# okenkovy_diskriminator.net
KiCad netlist of a schematic drawn in EAGLE
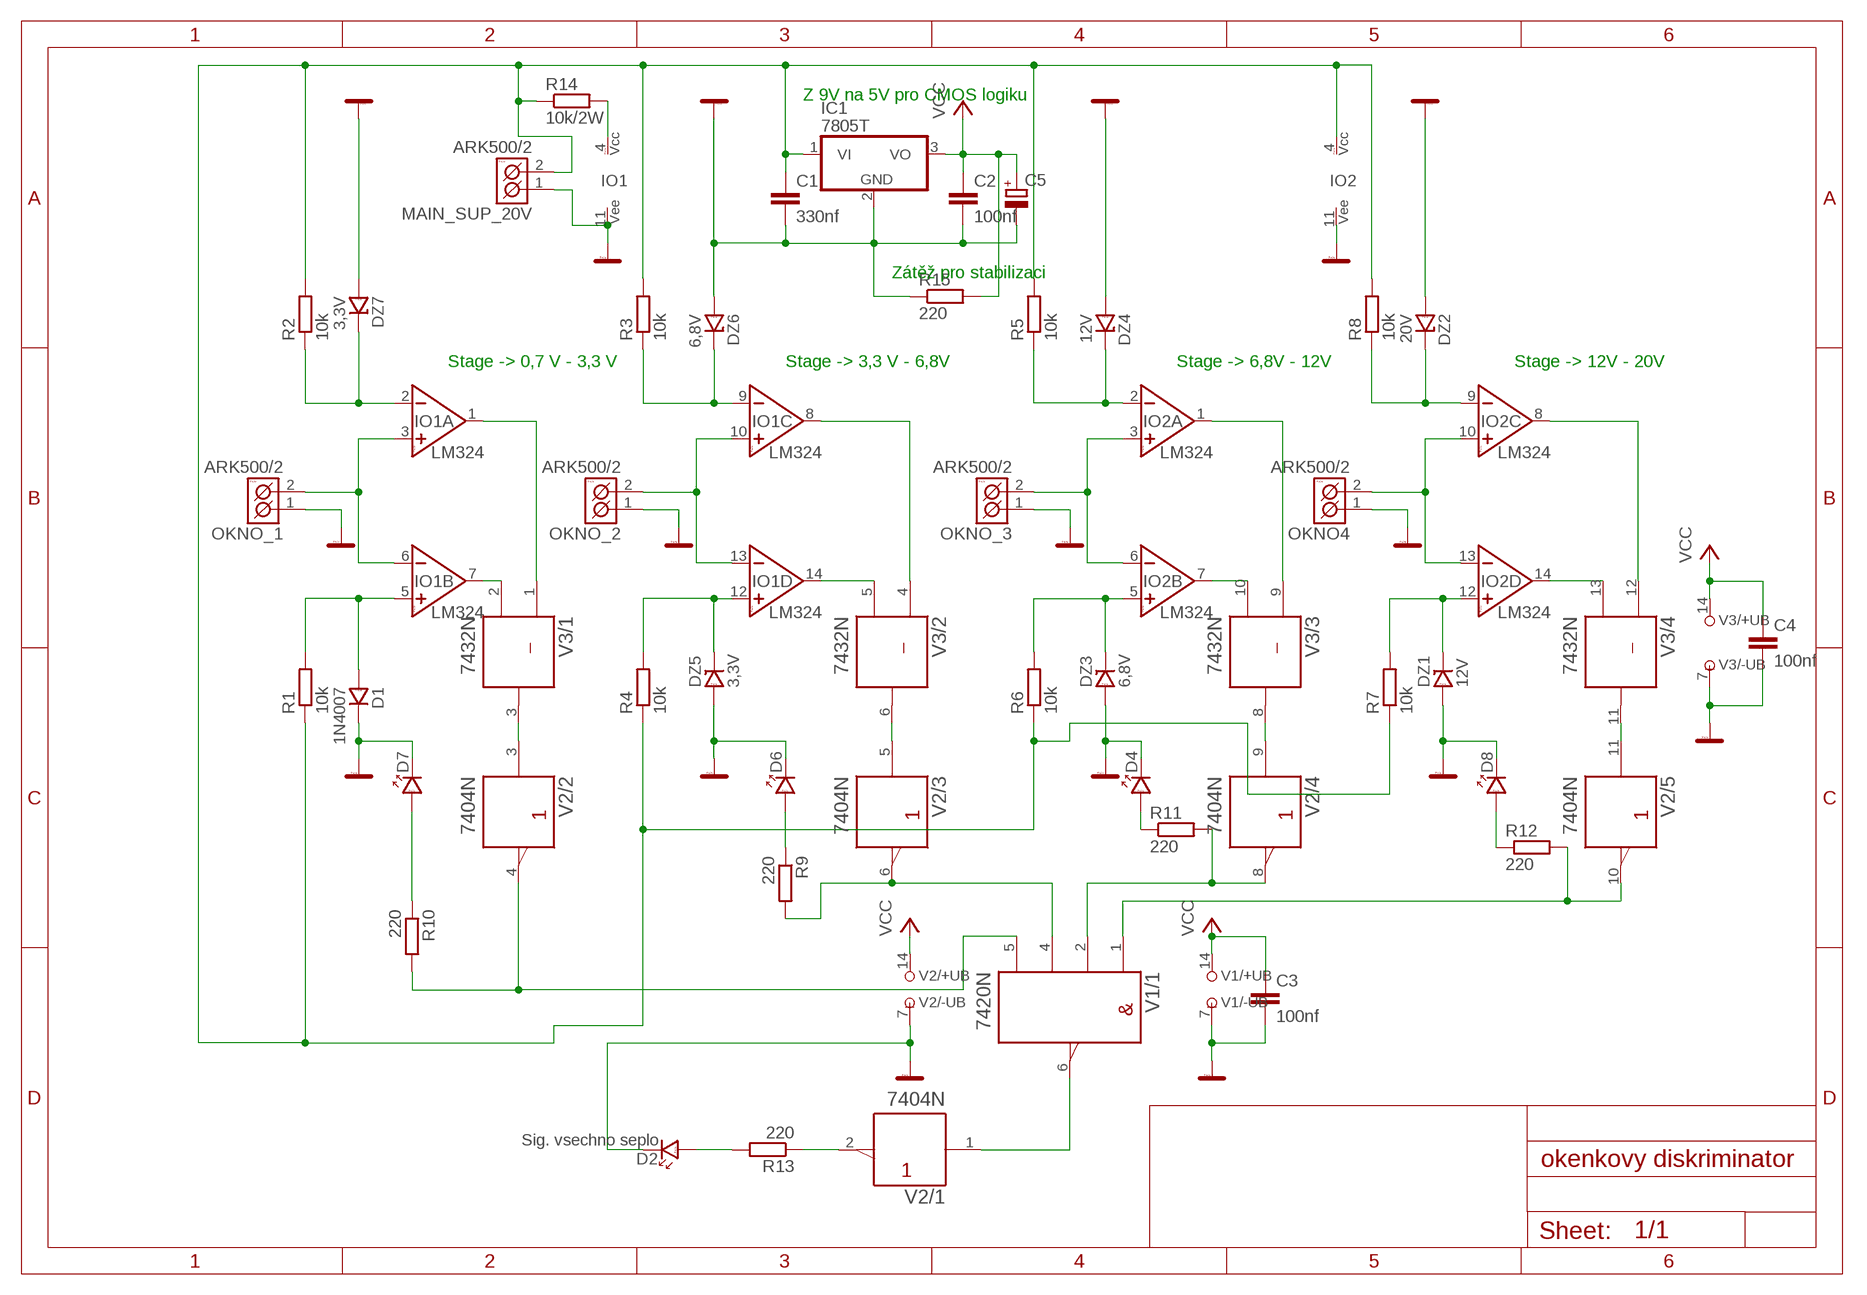
[diagram p0: schematic, sheet 1]

(export (version "E")
  (design (tool "Eeschema 10.0.6"))
  (components
    (comp (ref "C1")
      (value "330nf")
      (footprint "eagle-import:C050-030X075")
      (libsource (lib "eagle-import") (part "C-EU050-030X075"))
    )
    (comp (ref "C2")
      (value "100nf")
      (footprint "eagle-import:C050-030X075")
      (libsource (lib "eagle-import") (part "C-EU050-030X075"))
    )
    (comp (ref "C3")
      (value "100nf")
      (footprint "eagle-import:C050-025X075")
      (libsource (lib "eagle-import") (part "C-EU050-025X075"))
    )
    (comp (ref "C4")
      (value "100nf")
      (footprint "eagle-import:C050-025X075")
      (libsource (lib "eagle-import") (part "C-EU050-025X075"))
    )
    (comp (ref "C5")
      (value "CPOL-EUE2.5-5")
      (footprint "eagle-import:E2,5-5")
      (libsource (lib "eagle-import") (part "CPOL-EUE2.5-5"))
    )
    (comp (ref "D1")
      (value "1N4007")
      (footprint "eagle-import:DO41")
      (libsource (lib "eagle-import") (part "1N4007"))
    )
    (comp (ref "D2")
      (value "Sig. vsechno seplo")
      (footprint "eagle-import:LED_5")
      (libsource (lib "eagle-import") (part "LED_5"))
    )
    (comp (ref "D4")
      (value "LED_5")
      (footprint "eagle-import:LED_5")
      (libsource (lib "eagle-import") (part "LED_5"))
    )
    (comp (ref "D6")
      (value "LED_5")
      (footprint "eagle-import:LED_5")
      (libsource (lib "eagle-import") (part "LED_5"))
    )
    (comp (ref "D7")
      (value "LED_5")
      (footprint "eagle-import:LED_5")
      (libsource (lib "eagle-import") (part "LED_5"))
    )
    (comp (ref "D8")
      (value "LED_5")
      (footprint "eagle-import:LED_5")
      (libsource (lib "eagle-import") (part "LED_5"))
    )
    (comp (ref "DZ1")
      (value "12V")
      (footprint "eagle-import:DO35")
      (libsource (lib "eagle-import") (part "D-?-ZENERBZX85V_1,3W"))
    )
    (comp (ref "DZ2")
      (value "20V")
      (footprint "eagle-import:DO35")
      (libsource (lib "eagle-import") (part "D-?-ZENERBZX85V_1,3W"))
    )
    (comp (ref "DZ3")
      (value "6,8V")
      (footprint "eagle-import:DO35")
      (libsource (lib "eagle-import") (part "D-?-ZENERBZX85V_1,3W"))
    )
    (comp (ref "DZ4")
      (value "12V")
      (footprint "eagle-import:DO35")
      (libsource (lib "eagle-import") (part "D-?-ZENERBZX85V_1,3W"))
    )
    (comp (ref "DZ5")
      (value "3,3V")
      (footprint "eagle-import:DO35")
      (libsource (lib "eagle-import") (part "D-?-ZENERBZX85V_1,3W"))
    )
    (comp (ref "DZ6")
      (value "6,8V")
      (footprint "eagle-import:DO35")
      (libsource (lib "eagle-import") (part "D-?-ZENERBZX85V_1,3W"))
    )
    (comp (ref "DZ7")
      (value "3,3V")
      (footprint "eagle-import:DO35")
      (libsource (lib "eagle-import") (part "D-?-ZENERBZX85V_1,3W"))
    )
    (comp (ref "IC1")
      (value "7805T")
      (footprint "eagle-import:TO220H")
      (libsource (lib "eagle-import") (part "78T05"))
    )
    (comp (ref "IO1")
      (value "LM324")
      (footprint "eagle-import:DIL14")
      (libsource (lib "eagle-import") (part "LM324"))
    )
    (comp (ref "IO2")
      (value "LM324")
      (footprint "eagle-import:DIL14")
      (libsource (lib "eagle-import") (part "LM324"))
    )
    (comp (ref "MAIN_SUP_20V")
      (value "ARK500/2")
      (footprint "eagle-import:ARK500_2")
      (libsource (lib "eagle-import") (part "ARK500/2"))
    )
    (comp (ref "OKNO4")
      (value "ARK500/2")
      (footprint "eagle-import:ARK500_2")
      (libsource (lib "eagle-import") (part "ARK500/2"))
    )
    (comp (ref "OKNO_1")
      (value "ARK500/2")
      (footprint "eagle-import:ARK500_2")
      (libsource (lib "eagle-import") (part "ARK500/2"))
    )
    (comp (ref "OKNO_2")
      (value "ARK500/2")
      (footprint "eagle-import:ARK500_2")
      (libsource (lib "eagle-import") (part "ARK500/2"))
    )
    (comp (ref "OKNO_3")
      (value "ARK500/2")
      (footprint "eagle-import:ARK500_2")
      (libsource (lib "eagle-import") (part "ARK500/2"))
    )
    (comp (ref "R1")
      (value "10k")
      (footprint "eagle-import:0207_10")
      (libsource (lib "eagle-import") (part "R-EU_0207/10"))
    )
    (comp (ref "R2")
      (value "10k")
      (footprint "eagle-import:0207_10")
      (libsource (lib "eagle-import") (part "R-EU_0207/10"))
    )
    (comp (ref "R3")
      (value "10k")
      (footprint "eagle-import:0207_10")
      (libsource (lib "eagle-import") (part "R-EU_0207/10"))
    )
    (comp (ref "R4")
      (value "10k")
      (footprint "eagle-import:0207_10")
      (libsource (lib "eagle-import") (part "R-EU_0207/10"))
    )
    (comp (ref "R5")
      (value "10k")
      (footprint "eagle-import:0207_10")
      (libsource (lib "eagle-import") (part "R-EU_0207/10"))
    )
    (comp (ref "R6")
      (value "10k")
      (footprint "eagle-import:0207_10")
      (libsource (lib "eagle-import") (part "R-EU_0207/10"))
    )
    (comp (ref "R7")
      (value "10k")
      (footprint "eagle-import:0207_10")
      (libsource (lib "eagle-import") (part "R-EU_0207/10"))
    )
    (comp (ref "R8")
      (value "10k")
      (footprint "eagle-import:0207_10")
      (libsource (lib "eagle-import") (part "R-EU_0207/10"))
    )
    (comp (ref "R9")
      (value "220")
      (footprint "eagle-import:0207_10")
      (libsource (lib "eagle-import") (part "R-EU_0207/10"))
    )
    (comp (ref "R10")
      (value "220")
      (footprint "eagle-import:0207_10")
      (libsource (lib "eagle-import") (part "R-EU_0207/10"))
    )
    (comp (ref "R11")
      (value "220")
      (footprint "eagle-import:0207_10")
      (libsource (lib "eagle-import") (part "R-EU_0207/10"))
    )
    (comp (ref "R12")
      (value "220")
      (footprint "eagle-import:0207_10")
      (libsource (lib "eagle-import") (part "R-EU_0207/10"))
    )
    (comp (ref "R13")
      (value "220")
      (footprint "eagle-import:0207_10")
      (libsource (lib "eagle-import") (part "R-EU_0207/10"))
    )
    (comp (ref "R14")
      (value "10k/2W")
      (footprint "eagle-import:0414_15")
      (libsource (lib "eagle-import") (part "R-EU_0414/15"))
    )
    (comp (ref "R15")
      (value "220")
      (footprint "eagle-import:0207_10")
      (libsource (lib "eagle-import") (part "R-EU_0207/10"))
    )
    (comp (ref "V1")
      (value "7420N")
      (footprint "eagle-import:DIL14")
      (libsource (lib "eagle-import") (part "7420N"))
    )
    (comp (ref "V2")
      (value "7404N")
      (footprint "eagle-import:DIL14")
      (libsource (lib "eagle-import") (part "7404N"))
    )
    (comp (ref "V3")
      (value "7432N")
      (footprint "eagle-import:DIL14")
      (libsource (lib "eagle-import") (part "7432N"))
    )
  )
  (nets
    (net (code "1") (name "GND") (class "Default")
      (node (ref "C1") (pin "2") (pinfunction "2_2") (pintype "passive"))
      (node (ref "C2") (pin "2") (pinfunction "2_2") (pintype "passive"))
      (node (ref "C3") (pin "2") (pinfunction "2_2") (pintype "passive"))
      (node (ref "C4") (pin "2") (pinfunction "2_2") (pintype "passive"))
      (node (ref "C5") (pin "-") (pinfunction "-_-") (pintype "passive"))
      (node (ref "D1") (pin "K") (pinfunction "K_K") (pintype "passive"))
      (node (ref "D2") (pin "K") (pinfunction "K_K") (pintype "passive"))
      (node (ref "D4") (pin "K") (pinfunction "K_K") (pintype "passive"))
      (node (ref "D6") (pin "K") (pinfunction "K_K") (pintype "passive"))
      (node (ref "D7") (pin "K") (pinfunction "K_K") (pintype "passive"))
      (node (ref "D8") (pin "K") (pinfunction "K_K") (pintype "passive"))
      (node (ref "DZ1") (pin "A") (pinfunction "A_A") (pintype "passive"))
      (node (ref "DZ2") (pin "A") (pinfunction "A_A") (pintype "passive"))
      (node (ref "DZ3") (pin "A") (pinfunction "A_A") (pintype "passive"))
      (node (ref "DZ4") (pin "A") (pinfunction "A_A") (pintype "passive"))
      (node (ref "DZ5") (pin "A") (pinfunction "A_A") (pintype "passive"))
      (node (ref "DZ6") (pin "A") (pinfunction "A_A") (pintype "passive"))
      (node (ref "DZ7") (pin "A") (pinfunction "A_A") (pintype "passive"))
      (node (ref "IC1") (pin "2") (pinfunction "GND_2") (pintype "passive"))
      (node (ref "IO1") (pin "11") (pinfunction "VEE_11") (pintype "power_in"))
      (node (ref "IO2") (pin "11") (pinfunction "VEE_11") (pintype "power_in"))
      (node (ref "MAIN_SUP_20V") (pin "1") (pinfunction "K1_1") (pintype "passive"))
      (node (ref "OKNO4") (pin "1") (pinfunction "K1_1") (pintype "passive"))
      (node (ref "OKNO_1") (pin "1") (pinfunction "K1_1") (pintype "passive"))
      (node (ref "OKNO_2") (pin "1") (pinfunction "K1_1") (pintype "passive"))
      (node (ref "OKNO_3") (pin "1") (pinfunction "K1_1") (pintype "passive"))
      (node (ref "R15") (pin "1") (pinfunction "1_1") (pintype "passive"))
      (node (ref "V1") (pin "7") (pinfunction "-UB_7") (pintype "power_in"))
      (node (ref "V2") (pin "7") (pinfunction "-UB_7") (pintype "power_in"))
      (node (ref "V3") (pin "7") (pinfunction "-UB_7") (pintype "power_in"))
    )
    (net (code "2") (name "Net-(D2-PadA)") (class "Default")
      (node (ref "D2") (pin "A") (pinfunction "A_A") (pintype "passive"))
      (node (ref "R13") (pin "2") (pinfunction "2_2") (pintype "passive"))
    )
    (net (code "3") (name "Net-(D4-PadA)") (class "Default")
      (node (ref "D4") (pin "A") (pinfunction "A_A") (pintype "passive"))
      (node (ref "R11") (pin "1") (pinfunction "1_1") (pintype "passive"))
    )
    (net (code "4") (name "Net-(D6-PadA)") (class "Default")
      (node (ref "D6") (pin "A") (pinfunction "A_A") (pintype "passive"))
      (node (ref "R9") (pin "1") (pinfunction "1_1") (pintype "passive"))
    )
    (net (code "5") (name "Net-(D7-PadA)") (class "Default")
      (node (ref "D7") (pin "A") (pinfunction "A_A") (pintype "passive"))
      (node (ref "R10") (pin "1") (pinfunction "1_1") (pintype "passive"))
    )
    (net (code "6") (name "Net-(D8-PadA)") (class "Default")
      (node (ref "D8") (pin "A") (pinfunction "A_A") (pintype "passive"))
      (node (ref "R12") (pin "1") (pinfunction "1_1") (pintype "passive"))
    )
    (net (code "7") (name "Net-(IC1-VI)") (class "Default")
      (node (ref "C1") (pin "1") (pinfunction "1_1") (pintype "passive"))
      (node (ref "IC1") (pin "1") (pinfunction "VI_1") (pintype "input"))
      (node (ref "IO2") (pin "4") (pinfunction "VCC_4") (pintype "power_in"))
      (node (ref "MAIN_SUP_20V") (pin "2") (pinfunction "K2_2") (pintype "passive"))
      (node (ref "R1") (pin "1") (pinfunction "1_1") (pintype "passive"))
      (node (ref "R14") (pin "1") (pinfunction "1_1") (pintype "passive"))
      (node (ref "R2") (pin "2") (pinfunction "2_2") (pintype "passive"))
      (node (ref "R3") (pin "2") (pinfunction "2_2") (pintype "passive"))
      (node (ref "R4") (pin "1") (pinfunction "1_1") (pintype "passive"))
      (node (ref "R5") (pin "2") (pinfunction "2_2") (pintype "passive"))
      (node (ref "R6") (pin "1") (pinfunction "1_1") (pintype "passive"))
      (node (ref "R7") (pin "1") (pinfunction "1_1") (pintype "passive"))
      (node (ref "R8") (pin "2") (pinfunction "2_2") (pintype "passive"))
    )
    (net (code "8") (name "Net-(IO1A-IN-)") (class "Default")
      (node (ref "DZ7") (pin "K") (pinfunction "K_K") (pintype "passive"))
      (node (ref "IO1") (pin "2") (pinfunction "IN-_2") (pintype "input"))
      (node (ref "R2") (pin "1") (pinfunction "1_1") (pintype "passive"))
    )
    (net (code "9") (name "Net-(IO1A-NEIN+)") (class "Default")
      (node (ref "IO1") (pin "3") (pinfunction "NEIN+_3") (pintype "input"))
      (node (ref "IO1") (pin "6") (pinfunction "IN-_6") (pintype "input"))
      (node (ref "OKNO_1") (pin "2") (pinfunction "K2_2") (pintype "passive"))
    )
    (net (code "10") (name "Net-(IO1A-VYSTUP)") (class "Default")
      (node (ref "IO1") (pin "1") (pinfunction "VYSTUP_1") (pintype "output"))
      (node (ref "V3") (pin "1") (pinfunction "A_1") (pintype "input"))
    )
    (net (code "11") (name "Net-(IO1B-NEIN+)") (class "Default")
      (node (ref "D1") (pin "A") (pinfunction "A_A") (pintype "passive"))
      (node (ref "IO1") (pin "5") (pinfunction "NEIN+_5") (pintype "input"))
      (node (ref "R1") (pin "2") (pinfunction "2_2") (pintype "passive"))
    )
    (net (code "12") (name "Net-(IO1B-VYSTUP)") (class "Default")
      (node (ref "IO1") (pin "7") (pinfunction "VYSTUP_7") (pintype "output"))
      (node (ref "V3") (pin "2") (pinfunction "B_2") (pintype "input"))
    )
    (net (code "13") (name "Net-(IO1C-IN-)") (class "Default")
      (node (ref "DZ6") (pin "K") (pinfunction "K_K") (pintype "passive"))
      (node (ref "IO1") (pin "9") (pinfunction "IN-_9") (pintype "input"))
      (node (ref "R3") (pin "1") (pinfunction "1_1") (pintype "passive"))
    )
    (net (code "14") (name "Net-(IO1C-NEIN+)") (class "Default")
      (node (ref "IO1") (pin "10") (pinfunction "NEIN+_10") (pintype "input"))
      (node (ref "IO1") (pin "13") (pinfunction "IN-_13") (pintype "input"))
      (node (ref "OKNO_2") (pin "2") (pinfunction "K2_2") (pintype "passive"))
    )
    (net (code "15") (name "Net-(IO1C-VYSTUP)") (class "Default")
      (node (ref "IO1") (pin "8") (pinfunction "VYSTUP_8") (pintype "output"))
      (node (ref "V3") (pin "4") (pinfunction "A_4") (pintype "input"))
    )
    (net (code "16") (name "Net-(IO1D-NEIN+)") (class "Default")
      (node (ref "DZ5") (pin "K") (pinfunction "K_K") (pintype "passive"))
      (node (ref "IO1") (pin "12") (pinfunction "NEIN+_12") (pintype "input"))
      (node (ref "R4") (pin "2") (pinfunction "2_2") (pintype "passive"))
    )
    (net (code "17") (name "Net-(IO1D-VYSTUP)") (class "Default")
      (node (ref "IO1") (pin "14") (pinfunction "VYSTUP_14") (pintype "output"))
      (node (ref "V3") (pin "5") (pinfunction "B_5") (pintype "input"))
    )
    (net (code "18") (name "Net-(IO1E-VCC)") (class "Default")
      (node (ref "IO1") (pin "4") (pinfunction "VCC_4") (pintype "power_in"))
      (node (ref "R14") (pin "2") (pinfunction "2_2") (pintype "passive"))
    )
    (net (code "19") (name "Net-(IO2A-IN-)") (class "Default")
      (node (ref "DZ4") (pin "K") (pinfunction "K_K") (pintype "passive"))
      (node (ref "IO2") (pin "2") (pinfunction "IN-_2") (pintype "input"))
      (node (ref "R5") (pin "1") (pinfunction "1_1") (pintype "passive"))
    )
    (net (code "20") (name "Net-(IO2A-NEIN+)") (class "Default")
      (node (ref "IO2") (pin "3") (pinfunction "NEIN+_3") (pintype "input"))
      (node (ref "IO2") (pin "6") (pinfunction "IN-_6") (pintype "input"))
      (node (ref "OKNO_3") (pin "2") (pinfunction "K2_2") (pintype "passive"))
    )
    (net (code "21") (name "Net-(IO2A-VYSTUP)") (class "Default")
      (node (ref "IO2") (pin "1") (pinfunction "VYSTUP_1") (pintype "output"))
      (node (ref "V3") (pin "9") (pinfunction "A_9") (pintype "input"))
    )
    (net (code "22") (name "Net-(IO2B-NEIN+)") (class "Default")
      (node (ref "DZ3") (pin "K") (pinfunction "K_K") (pintype "passive"))
      (node (ref "IO2") (pin "5") (pinfunction "NEIN+_5") (pintype "input"))
      (node (ref "R6") (pin "2") (pinfunction "2_2") (pintype "passive"))
    )
    (net (code "23") (name "Net-(IO2B-VYSTUP)") (class "Default")
      (node (ref "IO2") (pin "7") (pinfunction "VYSTUP_7") (pintype "output"))
      (node (ref "V3") (pin "10") (pinfunction "B_10") (pintype "input"))
    )
    (net (code "24") (name "Net-(IO2C-IN-)") (class "Default")
      (node (ref "DZ2") (pin "K") (pinfunction "K_K") (pintype "passive"))
      (node (ref "IO2") (pin "9") (pinfunction "IN-_9") (pintype "input"))
      (node (ref "R8") (pin "1") (pinfunction "1_1") (pintype "passive"))
    )
    (net (code "25") (name "Net-(IO2C-NEIN+)") (class "Default")
      (node (ref "IO2") (pin "10") (pinfunction "NEIN+_10") (pintype "input"))
      (node (ref "IO2") (pin "13") (pinfunction "IN-_13") (pintype "input"))
      (node (ref "OKNO4") (pin "2") (pinfunction "K2_2") (pintype "passive"))
    )
    (net (code "26") (name "Net-(IO2C-VYSTUP)") (class "Default")
      (node (ref "IO2") (pin "8") (pinfunction "VYSTUP_8") (pintype "output"))
      (node (ref "V3") (pin "12") (pinfunction "A_12") (pintype "input"))
    )
    (net (code "27") (name "Net-(IO2D-NEIN+)") (class "Default")
      (node (ref "DZ1") (pin "K") (pinfunction "K_K") (pintype "passive"))
      (node (ref "IO2") (pin "12") (pinfunction "NEIN+_12") (pintype "input"))
      (node (ref "R7") (pin "2") (pinfunction "2_2") (pintype "passive"))
    )
    (net (code "28") (name "Net-(IO2D-VYSTUP)") (class "Default")
      (node (ref "IO2") (pin "14") (pinfunction "VYSTUP_14") (pintype "output"))
      (node (ref "V3") (pin "13") (pinfunction "B_13") (pintype "input"))
    )
    (net (code "29") (name "Net-(V1C-A)") (class "Default")
      (node (ref "R12") (pin "2") (pinfunction "2_2") (pintype "passive"))
      (node (ref "V1") (pin "1") (pinfunction "A_1") (pintype "input"))
      (node (ref "V2") (pin "10") (pinfunction "Y_10") (pintype "output"))
    )
    (net (code "30") (name "Net-(V1C-B)") (class "Default")
      (node (ref "R11") (pin "2") (pinfunction "2_2") (pintype "passive"))
      (node (ref "V1") (pin "2") (pinfunction "B_2") (pintype "input"))
      (node (ref "V2") (pin "8") (pinfunction "Y_8") (pintype "output"))
    )
    (net (code "31") (name "Net-(V1C-C)") (class "Default")
      (node (ref "R9") (pin "2") (pinfunction "2_2") (pintype "passive"))
      (node (ref "V1") (pin "4") (pinfunction "C_4") (pintype "input"))
      (node (ref "V2") (pin "6") (pinfunction "Y_6") (pintype "output"))
    )
    (net (code "32") (name "Net-(V1C-D)") (class "Default")
      (node (ref "R10") (pin "2") (pinfunction "2_2") (pintype "passive"))
      (node (ref "V1") (pin "5") (pinfunction "D_5") (pintype "input"))
      (node (ref "V2") (pin "4") (pinfunction "Y_4") (pintype "output"))
    )
    (net (code "33") (name "Net-(V1C-Y)") (class "Default")
      (node (ref "V1") (pin "6") (pinfunction "Y_6") (pintype "output"))
      (node (ref "V2") (pin "1") (pinfunction "A_1") (pintype "input"))
    )
    (net (code "34") (name "Net-(V2C-Y)") (class "Default")
      (node (ref "R13") (pin "1") (pinfunction "1_1") (pintype "passive"))
      (node (ref "V2") (pin "2") (pinfunction "Y_2") (pintype "output"))
    )
    (net (code "35") (name "Net-(V2D-A)") (class "Default")
      (node (ref "V2") (pin "3") (pinfunction "A_3") (pintype "input"))
      (node (ref "V3") (pin "3") (pinfunction "Y_3") (pintype "output"))
    )
    (net (code "36") (name "Net-(V2E-A)") (class "Default")
      (node (ref "V2") (pin "5") (pinfunction "A_5") (pintype "input"))
      (node (ref "V3") (pin "6") (pinfunction "Y_6") (pintype "output"))
    )
    (net (code "37") (name "Net-(V2F-A)") (class "Default")
      (node (ref "V2") (pin "9") (pinfunction "A_9") (pintype "input"))
      (node (ref "V3") (pin "8") (pinfunction "Y_8") (pintype "output"))
    )
    (net (code "38") (name "Net-(V2G-A)") (class "Default")
      (node (ref "V2") (pin "11") (pinfunction "A_11") (pintype "input"))
      (node (ref "V3") (pin "11") (pinfunction "Y_11") (pintype "output"))
    )
    (net (code "39") (name "VCC") (class "Default")
      (node (ref "C2") (pin "1") (pinfunction "1_1") (pintype "passive"))
      (node (ref "C3") (pin "1") (pinfunction "1_1") (pintype "passive"))
      (node (ref "C4") (pin "1") (pinfunction "1_1") (pintype "passive"))
      (node (ref "C5") (pin "+") (pinfunction "+_+") (pintype "passive"))
      (node (ref "IC1") (pin "3") (pinfunction "VO_3") (pintype "passive"))
      (node (ref "R15") (pin "2") (pinfunction "2_2") (pintype "passive"))
      (node (ref "V1") (pin "14") (pinfunction "+UB_14") (pintype "power_in"))
      (node (ref "V2") (pin "14") (pinfunction "+UB_14") (pintype "power_in"))
      (node (ref "V3") (pin "14") (pinfunction "+UB_14") (pintype "power_in"))
    )
  )
)
